# 05_Cardreader.net
KiCad netlist of a schematic drawn in Altium Designer
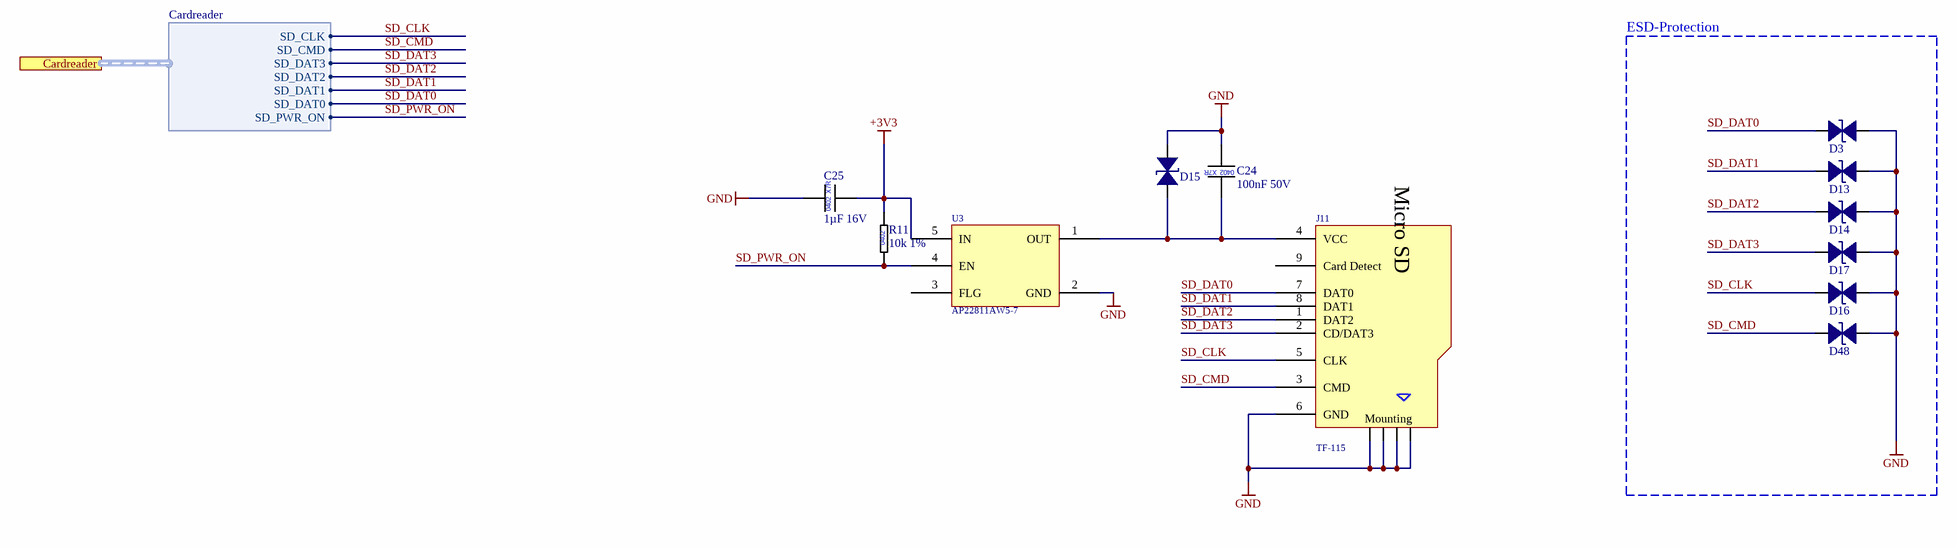
[diagram p0: 05_Cardreader.SchDoc]

(export (version "E")
  (design (tool "Eeschema 10.0.6"))
  (components
    (comp (ref "C24")
      (value "100nF 50V")
      (footprint "Cap:CAP_0402")
      (description "Multilayer Ceramic Capacitors MLCC - SMD/SMT 0402 50VDC")
      (libsource (lib "Cap") (part "CAP_0402_100nF_50V"))
    )
    (comp (ref "C25")
      (value "1µF 16V")
      (footprint "Cap:CAP_0402")
      (description "Multilayer Ceramic Capacitors MLCC - SMD/SMT 0402 16VDC")
      (libsource (lib "Cap") (part "CAP_0402_1µF_16V"))
    )
    (comp (ref "D3")
      (value "CESDP0402UC5VB")
      (footprint "Protec:TVS_0402")
      (description "Low Capacitance ESD Protection Diode 0402")
      (libsource (lib "Protec") (part "CESDP0402UC5VB_TVS Diode 0402"))
    )
    (comp (ref "D13")
      (value "CESDP0402UC5VB")
      (footprint "Protec:TVS_0402")
      (description "Low Capacitance ESD Protection Diode 0402")
      (libsource (lib "Protec") (part "CESDP0402UC5VB_TVS Diode 0402"))
    )
    (comp (ref "D14")
      (value "CESDP0402UC5VB")
      (footprint "Protec:TVS_0402")
      (description "Low Capacitance ESD Protection Diode 0402")
      (libsource (lib "Protec") (part "CESDP0402UC5VB_TVS Diode 0402"))
    )
    (comp (ref "D15")
      (value "CESDP0402UC5VB")
      (footprint "Protec:TVS_0402")
      (description "Low Capacitance ESD Protection Diode 0402")
      (libsource (lib "Protec") (part "CESDP0402UC5VB_TVS Diode 0402"))
    )
    (comp (ref "D16")
      (value "CESDP0402UC5VB")
      (footprint "Protec:TVS_0402")
      (description "Low Capacitance ESD Protection Diode 0402")
      (libsource (lib "Protec") (part "CESDP0402UC5VB_TVS Diode 0402"))
    )
    (comp (ref "D17")
      (value "CESDP0402UC5VB")
      (footprint "Protec:TVS_0402")
      (description "Low Capacitance ESD Protection Diode 0402")
      (libsource (lib "Protec") (part "CESDP0402UC5VB_TVS Diode 0402"))
    )
    (comp (ref "D48")
      (value "CESDP0402UC5VB")
      (footprint "Protec:TVS_0402")
      (description "Low Capacitance ESD Protection Diode 0402")
      (libsource (lib "Protec") (part "CESDP0402UC5VB_TVS Diode 0402"))
    )
    (comp (ref "J11")
      (value "TF-115")
      (footprint "conn:TF-115")
      (description "microSD™ Memory Card 8 connector&Ejector 14.5x14.75x1.85mm Card Sockets Connector")
      (libsource (lib "Conn") (part "TF-115_microSD™ Memory Card 8 connector"))
    )
    (comp (ref "R11")
      (value "10k 1%")
      (footprint "Res:RES_0402")
      (description "Thick Film Resistors - SMD 10kOhm 1%")
      (libsource (lib "Res") (part "RES_0402_10k_1%"))
    )
    (comp (ref "U3")
      (value "AP22811AW5-7")
      (footprint "Power:SOT95P285X140-5N")
      (description "Power Switch ICs - Power Distribution Load Switch")
      (libsource (lib "Power") (part "AP22811AW5-7_Power Switch ICs - Power Distribution Load Switch"))
    )
  )
  (nets
    (net (code "2") (name "+3V3") (class "Default")
      (node (ref "C25") (pin "2") (pinfunction "2_2") (pintype "passive"))
      (node (ref "R11") (pin "2") (pinfunction "2_2") (pintype "passive"))
      (node (ref "U3") (pin "5") (pinfunction "IN_5") (pintype "power_in"))
    )
    (net (code "3") (name "/SD_CLK") (class "Default")
      (node (ref "D16") (pin "1") (pinfunction "1_1") (pintype "passive"))
      (node (ref "J11") (pin "5") (pinfunction "CLK_5") (pintype "passive"))
    )
    (net (code "4") (name "/SD_CMD") (class "Default")
      (node (ref "D48") (pin "1") (pinfunction "1_1") (pintype "passive"))
      (node (ref "J11") (pin "3") (pinfunction "CMD_3") (pintype "passive"))
    )
    (net (code "5") (name "/SD_DAT0") (class "Default")
      (node (ref "D3") (pin "1") (pinfunction "1_1") (pintype "passive"))
      (node (ref "J11") (pin "7") (pinfunction "DAT0_7") (pintype "passive"))
    )
    (net (code "6") (name "/SD_DAT1") (class "Default")
      (node (ref "D13") (pin "1") (pinfunction "1_1") (pintype "passive"))
      (node (ref "J11") (pin "8") (pinfunction "DAT1_8") (pintype "passive"))
    )
    (net (code "7") (name "/SD_DAT2") (class "Default")
      (node (ref "D14") (pin "1") (pinfunction "1_1") (pintype "passive"))
      (node (ref "J11") (pin "1") (pinfunction "DAT2_1") (pintype "passive"))
    )
    (net (code "8") (name "/SD_DAT3") (class "Default")
      (node (ref "D17") (pin "1") (pinfunction "1_1") (pintype "passive"))
      (node (ref "J11") (pin "2") (pinfunction "CD/DAT3_2") (pintype "passive"))
    )
    (net (code "9") (name "/SD_PWR_ON") (class "Default")
      (node (ref "R11") (pin "1") (pinfunction "1_1") (pintype "passive"))
      (node (ref "U3") (pin "4") (pinfunction "EN_4") (pintype "passive"))
    )
    (net (code "11") (name "GND") (class "Default")
      (node (ref "C24") (pin "2") (pinfunction "2_2") (pintype "passive"))
      (node (ref "C25") (pin "1") (pinfunction "1_1") (pintype "passive"))
      (node (ref "D13") (pin "2") (pinfunction "2_2") (pintype "passive"))
      (node (ref "D14") (pin "2") (pinfunction "2_2") (pintype "passive"))
      (node (ref "D15") (pin "2") (pinfunction "2_2") (pintype "passive"))
      (node (ref "D16") (pin "2") (pinfunction "2_2") (pintype "passive"))
      (node (ref "D17") (pin "2") (pinfunction "2_2") (pintype "passive"))
      (node (ref "D3") (pin "2") (pinfunction "2_2") (pintype "passive"))
      (node (ref "D48") (pin "2") (pinfunction "2_2") (pintype "passive"))
      (node (ref "J11") (pin "10") (pinfunction "10_10") (pintype "passive"))
      (node (ref "J11") (pin "11") (pinfunction "11_11") (pintype "passive"))
      (node (ref "J11") (pin "12") (pinfunction "12_12") (pintype "passive"))
      (node (ref "J11") (pin "13") (pinfunction "13_13") (pintype "passive"))
      (node (ref "J11") (pin "6") (pinfunction "GND_6") (pintype "passive"))
      (node (ref "U3") (pin "2") (pinfunction "GND_2") (pintype "power_in"))
    )
    (net (code "12") (name "Net-(J11-VCC)") (class "Default")
      (node (ref "C24") (pin "1") (pinfunction "1_1") (pintype "passive"))
      (node (ref "D15") (pin "1") (pinfunction "1_1") (pintype "passive"))
      (node (ref "J11") (pin "4") (pinfunction "VCC_4") (pintype "passive"))
      (node (ref "U3") (pin "1") (pinfunction "OUT_1") (pintype "power_in"))
    )
    (net (code "13") (name "unconnected-(J11-Card_Detect-Pad9)") (class "Default")
      (node (ref "J11") (pin "9") (pinfunction "Card_Detect_9") (pintype "passive"))
    )
    (net (code "14") (name "unconnected-(U3-FLG-Pad3)") (class "Default")
      (node (ref "U3") (pin "3") (pinfunction "FLG_3") (pintype "open_collector"))
    )
  )
)
